# ConnectTech.net
KiCad netlist of a schematic drawn in Altium Designer
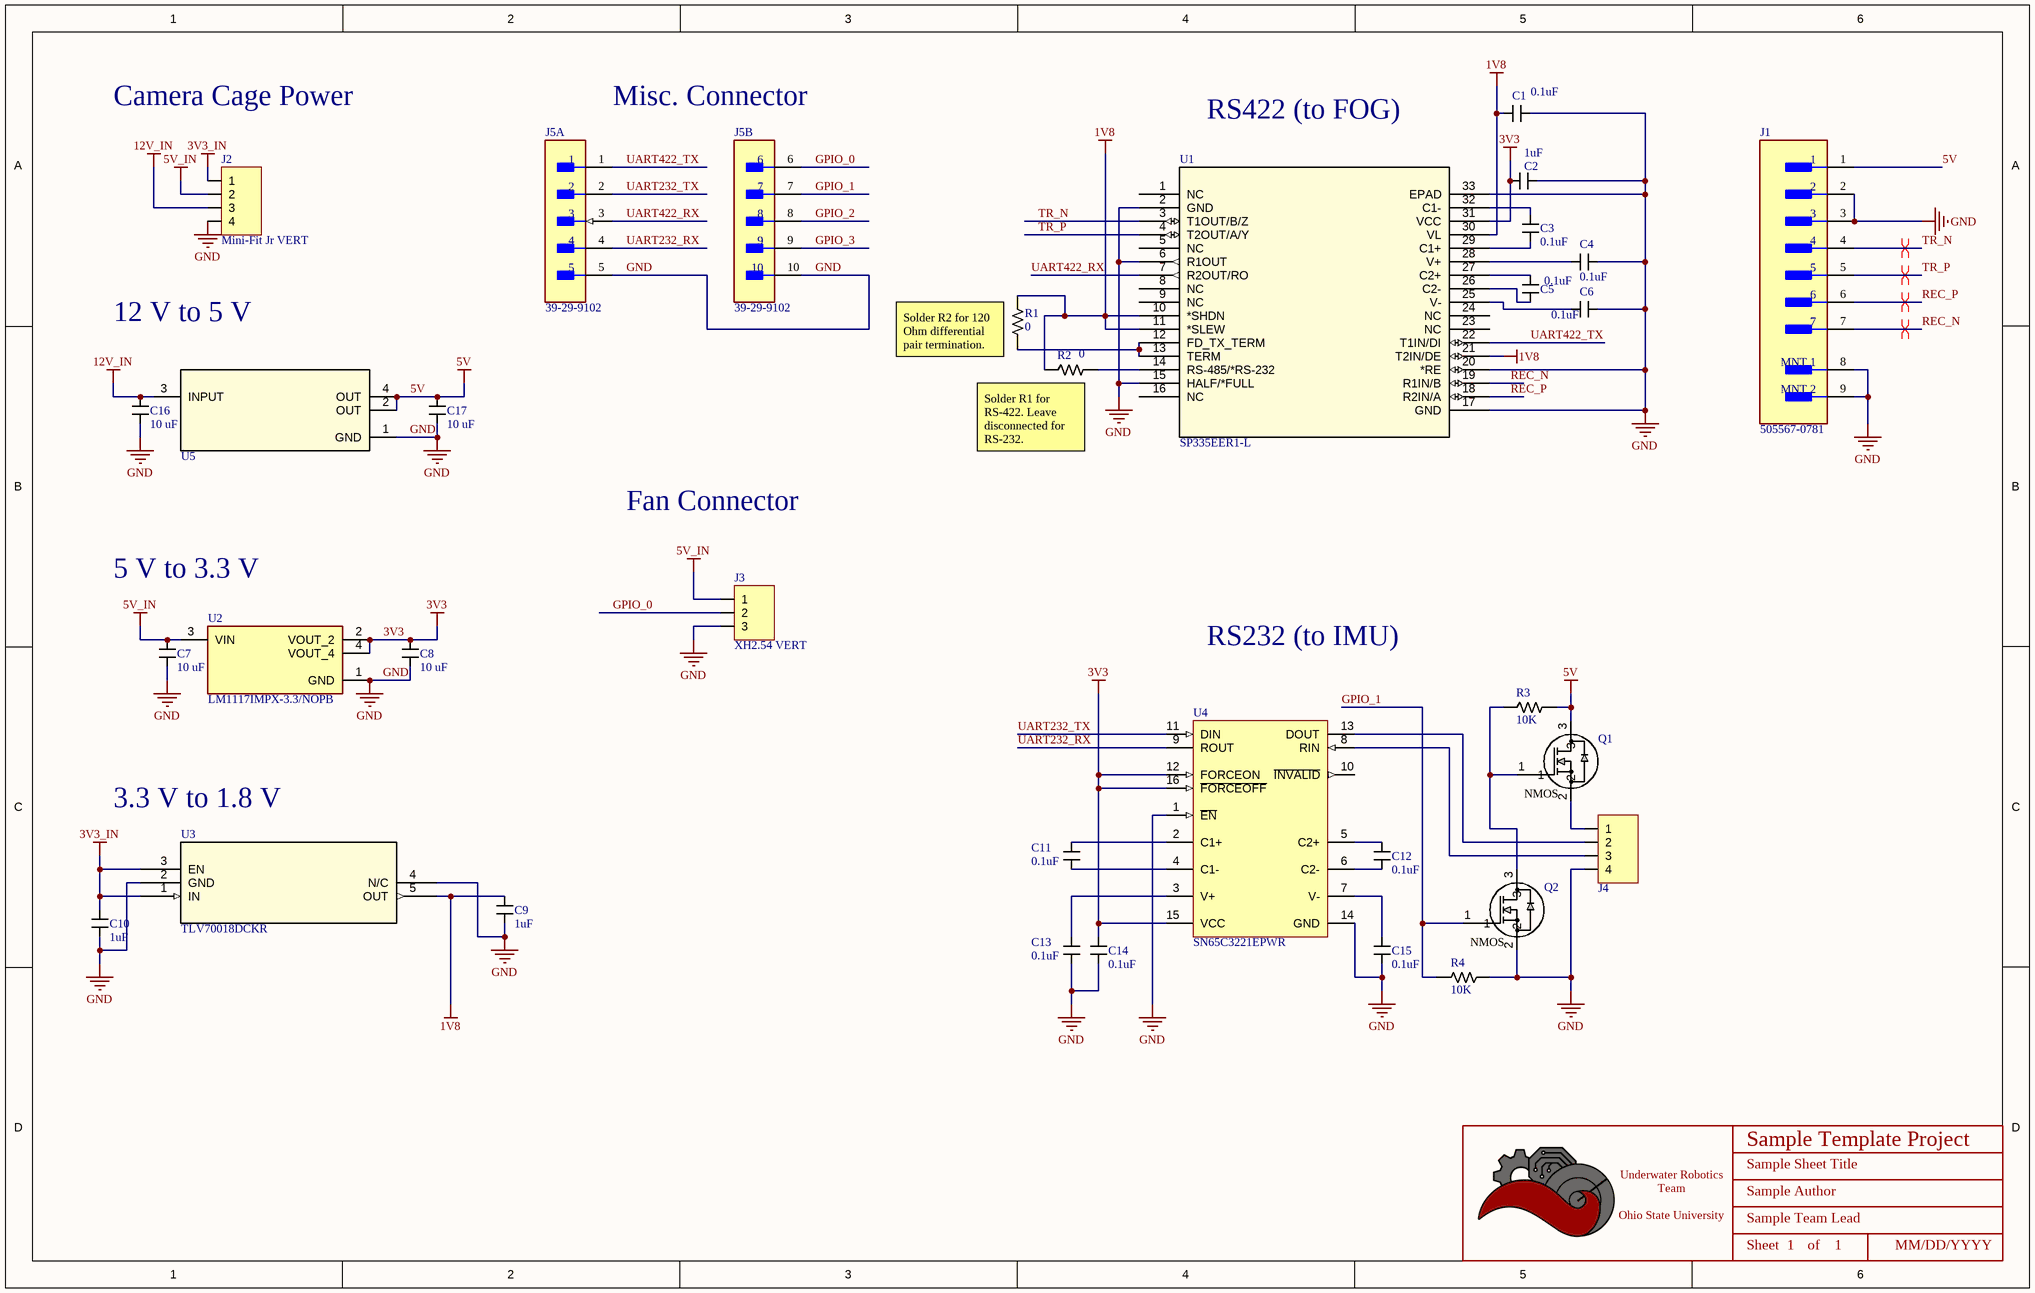
[diagram p0: ConnectTech.SchDoc]

(export (version "E")
  (design (tool "Eeschema 10.0.6"))
  (components
    (comp (ref "*")
      (value "Title_Block")
      (footprint "LOGO")
      (description "UWRT Schematic Title Block Template\r\n\r\nCreated June 2021, Dylan Trainor")
      (libsource (lib "UWRT") (part "Title_Block"))
    )
    (comp (ref "C1")
      (value "0.1uF")
      (footprint "CAPACITOR_0402")
      (description "Cap 100nF 25V +/-10%\r\nCeramic 0402")
      (fields
        (field (name "TOLERANCE") "+/- 10%")
        (field (name "VOLTAGE") "25V")
        (field (name "MADE BY") "Robert Pafford")
      )
      (libsource (lib "Capacitors") (part "CAPACITOR_0.1uF_0402"))
    )
    (comp (ref "C2")
      (value "1uF")
      (footprint "CAPACITOR_0402")
      (description "Cap 1uF 16V +/-10%\r\nCeramic 0402")
      (fields
        (field (name "TOLERANCE") "+/- 10%")
        (field (name "VOLTAGE") "16V")
        (field (name "MADE BY") "Robert Pafford")
      )
      (libsource (lib "Capacitors") (part "CAPACITOR_1uF_0402"))
    )
    (comp (ref "C3")
      (value "0.1uF")
      (footprint "CAPACITOR_0402")
      (description "Cap 100nF 25V +/-10%\r\nCeramic 0402")
      (fields
        (field (name "TOLERANCE") "+/- 10%")
        (field (name "VOLTAGE") "25V")
        (field (name "MADE BY") "Robert Pafford")
      )
      (libsource (lib "Capacitors") (part "CAPACITOR_0.1uF_0402"))
    )
    (comp (ref "C4")
      (value "0.1uF")
      (footprint "CAPACITOR_0402")
      (description "Cap 100nF 25V +/-10%\r\nCeramic 0402")
      (fields
        (field (name "TOLERANCE") "+/- 10%")
        (field (name "VOLTAGE") "25V")
        (field (name "MADE BY") "Robert Pafford")
      )
      (libsource (lib "Capacitors") (part "CAPACITOR_0.1uF_0402"))
    )
    (comp (ref "C5")
      (value "0.1uF")
      (footprint "CAPACITOR_0402")
      (description "Cap 100nF 25V +/-10%\r\nCeramic 0402")
      (fields
        (field (name "TOLERANCE") "+/- 10%")
        (field (name "VOLTAGE") "25V")
        (field (name "MADE BY") "Robert Pafford")
      )
      (libsource (lib "Capacitors") (part "CAPACITOR_0.1uF_0402"))
    )
    (comp (ref "C6")
      (value "0.1uF")
      (footprint "CAPACITOR_0402")
      (description "Cap 100nF 25V +/-10%\r\nCeramic 0402")
      (fields
        (field (name "TOLERANCE") "+/- 10%")
        (field (name "VOLTAGE") "25V")
        (field (name "MADE BY") "Robert Pafford")
      )
      (libsource (lib "Capacitors") (part "CAPACITOR_0.1uF_0402"))
    )
    (comp (ref "C7")
      (value "10uF Ceramic 6.3V")
      (footprint "CAPACITOR_0603")
      (description "Cap 10uF 6.3V +/-20%\r\nCeramic 0603")
      (fields
        (field (name "TOLERANCE") "+/- 20%")
        (field (name "VOLTAGE") "6.3V")
        (field (name "VALUE (UF)") "10 uF")
        (field (name "MADE BY") "Flip B")
      )
      (libsource (lib "Capacitors") (part "CAPACITOR_10uF_0603"))
    )
    (comp (ref "C8")
      (value "10uF Ceramic 6.3V")
      (footprint "CAPACITOR_0603")
      (description "Cap 10uF 6.3V +/-20%\r\nCeramic 0603")
      (fields
        (field (name "TOLERANCE") "+/- 20%")
        (field (name "VOLTAGE") "6.3V")
        (field (name "VALUE (UF)") "10 uF")
        (field (name "MADE BY") "Flip B")
      )
      (libsource (lib "Capacitors") (part "CAPACITOR_10uF_0603"))
    )
    (comp (ref "C9")
      (value "1uF")
      (footprint "CAPACITOR_0402")
      (description "Cap 1uF 16V +/-10%\r\nCeramic 0402")
      (fields
        (field (name "TOLERANCE") "+/- 10%")
        (field (name "VOLTAGE") "16V")
        (field (name "MADE BY") "Robert Pafford")
      )
      (libsource (lib "Capacitors") (part "CAPACITOR_1uF_0402"))
    )
    (comp (ref "C10")
      (value "1uF")
      (footprint "CAPACITOR_0402")
      (description "Cap 1uF 16V +/-10%\r\nCeramic 0402")
      (fields
        (field (name "TOLERANCE") "+/- 10%")
        (field (name "VOLTAGE") "16V")
        (field (name "MADE BY") "Robert Pafford")
      )
      (libsource (lib "Capacitors") (part "CAPACITOR_1uF_0402"))
    )
    (comp (ref "C11")
      (value "0.1uF")
      (footprint "CAPACITOR_0603")
      (description "Cap 100nF 6.3V +/-10%\r\nCeramic 0603")
      (fields
        (field (name "TOLERANCE") "+/- 10%")
        (field (name "VOLTAGE") "6.3V")
        (field (name "MADE BY") "Flip B")
      )
      (libsource (lib "Capacitors") (part "CAPACITOR_0.1uF_0603"))
    )
    (comp (ref "C12")
      (value "0.1uF")
      (footprint "CAPACITOR_0603")
      (description "Cap 100nF 6.3V +/-10%\r\nCeramic 0603")
      (fields
        (field (name "TOLERANCE") "+/- 10%")
        (field (name "VOLTAGE") "6.3V")
        (field (name "MADE BY") "Flip B")
      )
      (libsource (lib "Capacitors") (part "CAPACITOR_0.1uF_0603"))
    )
    (comp (ref "C13")
      (value "0.1uF")
      (footprint "CAPACITOR_0603")
      (description "Cap 100nF 6.3V +/-10%\r\nCeramic 0603")
      (fields
        (field (name "TOLERANCE") "+/- 10%")
        (field (name "VOLTAGE") "6.3V")
        (field (name "MADE BY") "Flip B")
      )
      (libsource (lib "Capacitors") (part "CAPACITOR_0.1uF_0603"))
    )
    (comp (ref "C14")
      (value "0.1uF")
      (footprint "CAPACITOR_0603")
      (description "Cap 100nF 6.3V +/-10%\r\nCeramic 0603")
      (fields
        (field (name "TOLERANCE") "+/- 10%")
        (field (name "VOLTAGE") "6.3V")
        (field (name "MADE BY") "Flip B")
      )
      (libsource (lib "Capacitors") (part "CAPACITOR_0.1uF_0603"))
    )
    (comp (ref "C15")
      (value "0.1uF")
      (footprint "CAPACITOR_0603")
      (description "Cap 100nF 6.3V +/-10%\r\nCeramic 0603")
      (fields
        (field (name "TOLERANCE") "+/- 10%")
        (field (name "VOLTAGE") "6.3V")
        (field (name "MADE BY") "Flip B")
      )
      (libsource (lib "Capacitors") (part "CAPACITOR_0.1uF_0603"))
    )
    (comp (ref "C16")
      (value "10uF Ceramic 6.3V")
      (footprint "CAPACITOR_0603")
      (description "Cap 10uF 6.3V +/-20%\r\nCeramic 0603")
      (fields
        (field (name "TOLERANCE") "+/- 20%")
        (field (name "VOLTAGE") "6.3V")
        (field (name "VALUE (UF)") "10 uF")
        (field (name "MADE BY") "Flip B")
      )
      (libsource (lib "Capacitors") (part "CAPACITOR_10uF_0603"))
    )
    (comp (ref "C17")
      (value "10uF Ceramic 6.3V")
      (footprint "CAPACITOR_0603")
      (description "Cap 10uF 6.3V +/-20%\r\nCeramic 0603")
      (fields
        (field (name "TOLERANCE") "+/- 20%")
        (field (name "VOLTAGE") "6.3V")
        (field (name "VALUE (UF)") "10 uF")
        (field (name "MADE BY") "Flip B")
      )
      (libsource (lib "Capacitors") (part "CAPACITOR_10uF_0603"))
    )
    (comp (ref "J1")
      (value "505567-0781")
      (footprint "FP-505567-0781-MFG")
      (libsource (lib "Altium Content Vault") (part "b0abd15a4b949e48c0a2e6945bb7dcd"))
    )
    (comp (ref "J2")
      (value "Mini-Fit Jr VERT")
      (footprint "CONN_MOLEX_MINIFIT JR_4 POS_VERT")
      (description "Molex Minifit Jr. 5566 \r\n4 Pos Vertical Natural")
      (fields (field (name "MANUFACTURER") "Molex") (field (name "CREATED BY") "Robert P"))
      (libsource (lib "Connectors") (part "CONN_MOLEX_MINIFIT JR_4POS_VERT"))
    )
    (comp (ref "J3")
      (value "XH2.54 VERT")
      (footprint "CONN_JST_XH254_3POS_VERT")
      (description "JST XH 2.54mm Pitch 3 Pos Vertical")
      (fields (field (name "MANUFACTURER") "JST") (field (name "CREATED BY") "Robert P"))
      (libsource (lib "Connectors") (part "CONN_JST_XH254_3POS_VERT"))
    )
    (comp (ref "J4")
      (value "XH2.54 VERT")
      (footprint "CONN_JST_XH254_4POS_VERT")
      (description "JST XH 2.54mm Pitch 4 Pos Vertical")
      (fields (field (name "MANUFACTURER") "JST") (field (name "CREATED BY") "Robert P"))
      (libsource (lib "Connectors") (part "CONN_JST_XH254_4POS_VERT"))
    )
    (comp (ref "J5")
      (value "39-29-9102")
      (footprint "FP-39-29-9102-MFG")
      (description "39-29-9102 Connector Wire to Board Header 10 Position 4.2mm Solder Straight Thru-Hole Tray")
      (libsource (lib "Altium Content Vault") (part "66d25172edd0fcb6412fc33dd95d2c2"))
    )
    (comp (ref "Q1")
      (value "MOSFET N-CH 30V 5.8A SOT-23-3")
      (footprint "SOT-23-3")
      (description "N-Channel 30 V 5.8A (Ta) 1.4W (Ta) Surface Mount SOT-23-3")
      (fields (field (name "MANUFACTURER _PART_NUMBER") "AO3404A") (field (name "CREATED BY") "Dylan T"))
      (libsource (lib "Transistors") (part "AO3404A"))
    )
    (comp (ref "Q2")
      (value "MOSFET N-CH 30V 5.8A SOT-23-3")
      (footprint "SOT-23-3")
      (description "N-Channel 30 V 5.8A (Ta) 1.4W (Ta) Surface Mount SOT-23-3")
      (fields (field (name "MANUFACTURER _PART_NUMBER") "AO3404A") (field (name "CREATED BY") "Dylan T"))
      (libsource (lib "Transistors") (part "AO3404A"))
    )
    (comp (ref "R1")
      (value "0 Ohm 1% 1/16W")
      (footprint "RESISTOR_0402")
      (description "RES 0 OHM 1% 1/16W 0402")
      (fields
        (field (name "TOLERANCE") "+/- 1%")
        (field (name "VALUE  (OHMS)") "0")
        (field (name "MADE BY") "Robert Pafford")
      )
      (libsource (lib "Resistors") (part "RESISTOR_0_0402"))
    )
    (comp (ref "R2")
      (value "0 Ohm 1% 1/16W")
      (footprint "RESISTOR_0402")
      (description "RES 0 OHM 1% 1/16W 0402")
      (fields
        (field (name "TOLERANCE") "+/- 1%")
        (field (name "VALUE  (OHMS)") "0")
        (field (name "MADE BY") "Robert Pafford")
      )
      (libsource (lib "Resistors") (part "RESISTOR_0_0402"))
    )
    (comp (ref "R3")
      (value "10k Ohm 5% 1/10W")
      (footprint "RESISTOR_0603")
      (description "RES 10k OHM 5% 1/10W 0603")
      (fields
        (field (name "TOLERANCE") "+/- 5%")
        (field (name "VALUE  (OHMS)") "10K")
        (field (name "MADE BY") "Robert Pafford")
      )
      (libsource (lib "Resistors") (part "RESISTOR_10K_0603"))
    )
    (comp (ref "R4")
      (value "10k Ohm 5% 1/10W")
      (footprint "RESISTOR_0603")
      (description "RES 10k OHM 5% 1/10W 0603")
      (fields
        (field (name "TOLERANCE") "+/- 5%")
        (field (name "VALUE  (OHMS)") "10K")
        (field (name "MADE BY") "Robert Pafford")
      )
      (libsource (lib "Resistors") (part "RESISTOR_10K_0603"))
    )
    (comp (ref "U1")
      (value "SP335EER1-L")
      (footprint "QFN-32")
      (description "1/1, 2/2 Transceiver Full RS232, RS422, RS485 32-QFN (5x5)")
      (fields (field (name "CREATED BY") "Ethan Rosati") (field (name "REVIEWED BY") "*"))
      (libsource (lib "Integrated Circuits") (part "SP335EER1-L"))
    )
    (comp (ref "U2")
      (value "LM1117IMPX-3.3/NOPB")
      (footprint "SOT-223-4")
      (description "800-mA 15-V linear voltage regulator 4-SOT-223 -40 to 125")
      (fields (field (name "MF") "Texas Instruments"))
      (libsource (lib "Integrated Circuits") (part "LM1117IMPX-3.3/NOPB"))
    )
    (comp (ref "U3")
      (value "TLV70018DCKR")
      (footprint "SOT-353")
      (description "Fixed Positive LDO Regulator, 1.8V, PMOS, PDSO5")
      (fields (field (name "MADE BY") "Ethan Rosati") (field (name "REVIEWED BY") "*"))
      (libsource (lib "Integrated Circuits") (part "TLV70018DCKR"))
    )
    (comp (ref "U4")
      (value "SN65C3221EPWR")
      (footprint "PW0016A_M")
      (libsource (lib "Altium Content Vault") (part "TI-SN65C3221E-TSSOP_PW-16"))
    )
    (comp (ref "U5")
      (value "LM1117IMPX-5.0/NOPB")
      (footprint "SOT-223-4")
      (description "IC REG LINEAR 5V 800MA SOT223-4")
      (libsource (lib "Integrated Circuits") (part "LM1117IMPX-5.0/NOPB"))
    )
  )
  (nets
    (net (code "1") (name "/GPIO_0") (class "Default")
      (node (ref "J3") (pin "2") (pinfunction "2_2") (pintype "passive"))
      (node (ref "J5") (pin "6") (pinfunction "6_6") (pintype "passive"))
    )
    (net (code "2") (name "/GPIO_1") (class "Default")
      (node (ref "J5") (pin "7") (pinfunction "7_7") (pintype "passive"))
      (node (ref "Q2") (pin "1") (pinfunction "1_1") (pintype "passive"))
      (node (ref "R4") (pin "1") (pinfunction "1_1") (pintype "passive"))
    )
    (net (code "3") (name "/GPIO_2") (class "Default")
      (node (ref "J5") (pin "8") (pinfunction "8_8") (pintype "passive"))
    )
    (net (code "4") (name "/GPIO_3") (class "Default")
      (node (ref "J5") (pin "9") (pinfunction "9_9") (pintype "passive"))
    )
    (net (code "5") (name "/REC_N") (class "Default")
      (node (ref "J1") (pin "7") (pinfunction "7_7") (pintype "passive"))
      (node (ref "U1") (pin "19") (pinfunction "R1IN/B_19") (pintype "bidirectional"))
    )
    (net (code "6") (name "/REC_P") (class "Default")
      (node (ref "J1") (pin "6") (pinfunction "6_6") (pintype "passive"))
      (node (ref "U1") (pin "18") (pinfunction "R2IN/A_18") (pintype "bidirectional"))
    )
    (net (code "7") (name "/TR_N") (class "Default")
      (node (ref "J1") (pin "4") (pinfunction "4_4") (pintype "passive"))
      (node (ref "U1") (pin "3") (pinfunction "T1OUT/B/Z_3") (pintype "bidirectional"))
    )
    (net (code "8") (name "/TR_P") (class "Default")
      (node (ref "J1") (pin "5") (pinfunction "5_5") (pintype "passive"))
      (node (ref "U1") (pin "4") (pinfunction "T2OUT/A/Y_4") (pintype "bidirectional"))
    )
    (net (code "9") (name "/UART232_RX") (class "Default")
      (node (ref "J5") (pin "4") (pinfunction "4_4") (pintype "passive"))
      (node (ref "U4") (pin "9") (pinfunction "ROUT_9") (pintype "tri_state"))
    )
    (net (code "10") (name "/UART232_TX") (class "Default")
      (node (ref "J5") (pin "2") (pinfunction "2_2") (pintype "passive"))
      (node (ref "U4") (pin "11") (pinfunction "DIN_11") (pintype "input"))
    )
    (net (code "11") (name "/UART422_RX") (class "Default")
      (node (ref "J5") (pin "3") (pinfunction "3_3") (pintype "input"))
      (node (ref "U1") (pin "7") (pinfunction "R2OUT/RO_7") (pintype "output"))
    )
    (net (code "12") (name "/UART422_TX") (class "Default")
      (node (ref "J5") (pin "1") (pinfunction "1_1") (pintype "passive"))
      (node (ref "U1") (pin "22") (pinfunction "T1IN/DI_22") (pintype "bidirectional"))
    )
    (net (code "13") (name "1V8") (class "Default")
      (node (ref "C1") (pin "1") (pinfunction "1_1") (pintype "passive"))
      (node (ref "C9") (pin "1") (pinfunction "1_1") (pintype "passive"))
      (node (ref "R1") (pin "2") (pinfunction "2_2") (pintype "passive"))
      (node (ref "R2") (pin "2") (pinfunction "2_2") (pintype "passive"))
      (node (ref "U1") (pin "10") (pinfunction "*SHDN_10") (pintype "passive"))
      (node (ref "U1") (pin "11") (pinfunction "*SLEW_11") (pintype "passive"))
      (node (ref "U1") (pin "21") (pinfunction "T2IN/DE_21") (pintype "bidirectional"))
      (node (ref "U1") (pin "30") (pinfunction "VL_30") (pintype "power_in"))
      (node (ref "U3") (pin "5") (pinfunction "OUT_5") (pintype "output"))
    )
    (net (code "14") (name "3V3") (class "Default")
      (node (ref "C14") (pin "1") (pinfunction "1_1") (pintype "passive"))
      (node (ref "C2") (pin "1") (pinfunction "1_1") (pintype "passive"))
      (node (ref "C8") (pin "1") (pinfunction "1_1") (pintype "passive"))
      (node (ref "U1") (pin "31") (pinfunction "VCC_31") (pintype "power_in"))
      (node (ref "U2") (pin "2") (pinfunction "VOUT_2_2") (pintype "power_in"))
      (node (ref "U2") (pin "4") (pinfunction "VOUT_4_4") (pintype "power_in"))
      (node (ref "U4") (pin "12") (pinfunction "FORCEON_12") (pintype "input"))
      (node (ref "U4") (pin "15") (pinfunction "VCC_15") (pintype "power_in"))
      (node (ref "U4") (pin "16") (pinfunction "~{FORCEOFF}_16") (pintype "input"))
    )
    (net (code "15") (name "3V3_IN") (class "Default")
      (node (ref "C10") (pin "1") (pinfunction "1_1") (pintype "passive"))
      (node (ref "J2") (pin "1") (pinfunction "1_1") (pintype "passive"))
      (node (ref "U3") (pin "1") (pinfunction "IN_1") (pintype "input"))
      (node (ref "U3") (pin "3") (pinfunction "EN_3") (pintype "passive"))
    )
    (net (code "16") (name "5V") (class "Default")
      (node (ref "C17") (pin "1") (pinfunction "1_1") (pintype "passive"))
      (node (ref "J1") (pin "1") (pinfunction "1_1") (pintype "passive"))
      (node (ref "Q1") (pin "3") (pinfunction "3_3") (pintype "passive"))
      (node (ref "R3") (pin "1") (pinfunction "1_1") (pintype "passive"))
      (node (ref "U5") (pin "2") (pinfunction "OUT_2") (pintype "power_in"))
      (node (ref "U5") (pin "4") (pinfunction "OUT_4") (pintype "power_in"))
    )
    (net (code "17") (name "5V_IN") (class "Default")
      (node (ref "C7") (pin "1") (pinfunction "1_1") (pintype "passive"))
      (node (ref "J2") (pin "2") (pinfunction "2_2") (pintype "passive"))
      (node (ref "J3") (pin "1") (pinfunction "1_1") (pintype "passive"))
      (node (ref "U2") (pin "3") (pinfunction "VIN_3") (pintype "power_in"))
    )
    (net (code "18") (name "12V_IN") (class "Default")
      (node (ref "C16") (pin "1") (pinfunction "1_1") (pintype "passive"))
      (node (ref "J2") (pin "3") (pinfunction "3_3") (pintype "passive"))
      (node (ref "U5") (pin "3") (pinfunction "INPUT_3") (pintype "power_in"))
    )
    (net (code "19") (name "GND") (class "Default")
      (node (ref "C1") (pin "2") (pinfunction "2_2") (pintype "passive"))
      (node (ref "C10") (pin "2") (pinfunction "2_2") (pintype "passive"))
      (node (ref "C13") (pin "2") (pinfunction "2_2") (pintype "passive"))
      (node (ref "C14") (pin "2") (pinfunction "2_2") (pintype "passive"))
      (node (ref "C15") (pin "2") (pinfunction "2_2") (pintype "passive"))
      (node (ref "C16") (pin "2") (pinfunction "2_2") (pintype "passive"))
      (node (ref "C17") (pin "2") (pinfunction "2_2") (pintype "passive"))
      (node (ref "C2") (pin "2") (pinfunction "2_2") (pintype "passive"))
      (node (ref "C4") (pin "2") (pinfunction "2_2") (pintype "passive"))
      (node (ref "C6") (pin "2") (pinfunction "2_2") (pintype "passive"))
      (node (ref "C7") (pin "2") (pinfunction "2_2") (pintype "passive"))
      (node (ref "C8") (pin "2") (pinfunction "2_2") (pintype "passive"))
      (node (ref "C9") (pin "2") (pinfunction "2_2") (pintype "passive"))
      (node (ref "J1") (pin "2") (pinfunction "2_2") (pintype "passive"))
      (node (ref "J1") (pin "3") (pinfunction "3_3") (pintype "passive"))
      (node (ref "J1") (pin "8") (pinfunction "MNT_1_8") (pintype "passive"))
      (node (ref "J1") (pin "9") (pinfunction "MNT_2_9") (pintype "passive"))
      (node (ref "J2") (pin "4") (pinfunction "4_4") (pintype "passive"))
      (node (ref "J3") (pin "3") (pinfunction "3_3") (pintype "passive"))
      (node (ref "J4") (pin "4") (pinfunction "4_4") (pintype "passive"))
      (node (ref "J5") (pin "10") (pinfunction "10_10") (pintype "passive"))
      (node (ref "J5") (pin "5") (pinfunction "5_5") (pintype "passive"))
      (node (ref "Q2") (pin "2") (pinfunction "2_2") (pintype "passive"))
      (node (ref "R4") (pin "2") (pinfunction "2_2") (pintype "passive"))
      (node (ref "U1") (pin "15") (pinfunction "HALF/*FULL_15") (pintype "passive"))
      (node (ref "U1") (pin "17") (pinfunction "GND_17") (pintype "power_in"))
      (node (ref "U1") (pin "2") (pinfunction "GND_2") (pintype "power_in"))
      (node (ref "U1") (pin "20") (pinfunction "*RE_20") (pintype "bidirectional"))
      (node (ref "U1") (pin "33") (pinfunction "EPAD_33") (pintype "passive"))
      (node (ref "U1") (pin "6") (pinfunction "R1OUT_6") (pintype "output"))
      (node (ref "U2") (pin "1") (pinfunction "GND_1") (pintype "power_in"))
      (node (ref "U3") (pin "2") (pinfunction "GND_2") (pintype "passive"))
      (node (ref "U3") (pin "4") (pinfunction "N/C_4") (pintype "power_in"))
      (node (ref "U4") (pin "1") (pinfunction "~{EN}_1") (pintype "input"))
      (node (ref "U4") (pin "14") (pinfunction "GND_14") (pintype "power_in"))
      (node (ref "U5") (pin "1") (pinfunction "GND_1") (pintype "power_in"))
    )
    (net (code "20") (name "Net-(J4-Pad1)") (class "Default")
      (node (ref "J4") (pin "1") (pinfunction "1_1") (pintype "passive"))
      (node (ref "Q1") (pin "2") (pinfunction "2_2") (pintype "passive"))
    )
    (net (code "21") (name "Net-(Q1-Pad1)") (class "Default")
      (node (ref "Q1") (pin "1") (pinfunction "1_1") (pintype "passive"))
      (node (ref "Q2") (pin "3") (pinfunction "3_3") (pintype "passive"))
      (node (ref "R3") (pin "2") (pinfunction "2_2") (pintype "passive"))
    )
    (net (code "22") (name "Net-(U1-C1+)") (class "Default")
      (node (ref "C3") (pin "2") (pinfunction "2_2") (pintype "passive"))
      (node (ref "U1") (pin "29") (pinfunction "C1+_29") (pintype "passive"))
    )
    (net (code "23") (name "Net-(U1-C1-)") (class "Default")
      (node (ref "C3") (pin "1") (pinfunction "1_1") (pintype "passive"))
      (node (ref "U1") (pin "32") (pinfunction "C1-_32") (pintype "passive"))
    )
    (net (code "24") (name "Net-(U1-C2+)") (class "Default")
      (node (ref "C5") (pin "1") (pinfunction "1_1") (pintype "passive"))
      (node (ref "U1") (pin "27") (pinfunction "C2+_27") (pintype "passive"))
    )
    (net (code "25") (name "Net-(U1-C2-)") (class "Default")
      (node (ref "C5") (pin "2") (pinfunction "2_2") (pintype "passive"))
      (node (ref "U1") (pin "26") (pinfunction "C2-_26") (pintype "passive"))
    )
    (net (code "26") (name "Net-(U1-FD_TX_TERM)") (class "Default")
      (node (ref "R1") (pin "1") (pinfunction "1_1") (pintype "passive"))
      (node (ref "U1") (pin "12") (pinfunction "FD_TX_TERM_12") (pintype "passive"))
      (node (ref "U1") (pin "13") (pinfunction "TERM_13") (pintype "passive"))
    )
    (net (code "27") (name "Net-(U1-RS-485{slash}*RS-232)") (class "Default")
      (node (ref "R2") (pin "1") (pinfunction "1_1") (pintype "passive"))
      (node (ref "U1") (pin "14") (pinfunction "RS-485/*RS-232_14") (pintype "passive"))
    )
    (net (code "28") (name "Net-(U1-V+)") (class "Default")
      (node (ref "C4") (pin "1") (pinfunction "1_1") (pintype "passive"))
      (node (ref "U1") (pin "28") (pinfunction "V+_28") (pintype "power_in"))
    )
    (net (code "29") (name "Net-(U1-V-)") (class "Default")
      (node (ref "C6") (pin "1") (pinfunction "1_1") (pintype "passive"))
      (node (ref "U1") (pin "25") (pinfunction "V-_25") (pintype "power_in"))
    )
    (net (code "30") (name "Net-(U4-C1+)") (class "Default")
      (node (ref "C11") (pin "1") (pinfunction "1_1") (pintype "passive"))
      (node (ref "U4") (pin "2") (pinfunction "C1+_2") (pintype "passive"))
    )
    (net (code "31") (name "Net-(U4-C1-)") (class "Default")
      (node (ref "C11") (pin "2") (pinfunction "2_2") (pintype "passive"))
      (node (ref "U4") (pin "4") (pinfunction "C1-_4") (pintype "passive"))
    )
    (net (code "32") (name "Net-(U4-C2+)") (class "Default")
      (node (ref "C12") (pin "1") (pinfunction "1_1") (pintype "passive"))
      (node (ref "U4") (pin "5") (pinfunction "C2+_5") (pintype "passive"))
    )
    (net (code "33") (name "Net-(U4-C2-)") (class "Default")
      (node (ref "C12") (pin "2") (pinfunction "2_2") (pintype "passive"))
      (node (ref "U4") (pin "6") (pinfunction "C2-_6") (pintype "passive"))
    )
    (net (code "34") (name "Net-(U4-DOUT)") (class "Default")
      (node (ref "J4") (pin "2") (pinfunction "2_2") (pintype "passive"))
      (node (ref "U4") (pin "13") (pinfunction "DOUT_13") (pintype "tri_state"))
    )
    (net (code "35") (name "Net-(U4-RIN)") (class "Default")
      (node (ref "J4") (pin "3") (pinfunction "3_3") (pintype "passive"))
      (node (ref "U4") (pin "8") (pinfunction "RIN_8") (pintype "input"))
    )
    (net (code "36") (name "Net-(U4-V+)") (class "Default")
      (node (ref "C13") (pin "1") (pinfunction "1_1") (pintype "passive"))
      (node (ref "U4") (pin "3") (pinfunction "V+_3") (pintype "power_in"))
    )
    (net (code "37") (name "Net-(U4-V-)") (class "Default")
      (node (ref "C15") (pin "1") (pinfunction "1_1") (pintype "passive"))
      (node (ref "U4") (pin "7") (pinfunction "V-_7") (pintype "power_in"))
    )
    (net (code "38") (name "unconnected-(U1-NC-Pad1)") (class "Default")
      (node (ref "U1") (pin "1") (pinfunction "NC_1") (pintype "passive"))
    )
    (net (code "39") (name "unconnected-(U1-NC-Pad5)") (class "Default")
      (node (ref "U1") (pin "5") (pinfunction "NC_5") (pintype "passive"))
    )
    (net (code "40") (name "unconnected-(U1-NC-Pad8)") (class "Default")
      (node (ref "U1") (pin "8") (pinfunction "NC_8") (pintype "passive"))
    )
    (net (code "41") (name "unconnected-(U1-NC-Pad9)") (class "Default")
      (node (ref "U1") (pin "9") (pinfunction "NC_9") (pintype "passive"))
    )
    (net (code "42") (name "unconnected-(U1-NC-Pad16)") (class "Default")
      (node (ref "U1") (pin "16") (pinfunction "NC_16") (pintype "passive"))
    )
    (net (code "43") (name "unconnected-(U1-NC-Pad23)") (class "Default")
      (node (ref "U1") (pin "23") (pinfunction "NC_23") (pintype "passive"))
    )
    (net (code "44") (name "unconnected-(U1-NC-Pad24)") (class "Default")
      (node (ref "U1") (pin "24") (pinfunction "NC_24") (pintype "passive"))
    )
    (net (code "45") (name "unconnected-(U4-~{INVALID}-Pad10)") (class "Default")
      (node (ref "U4") (pin "10") (pinfunction "~{INVALID}_10") (pintype "output"))
    )
  )
)
